# vmon-and-imon-measurements-hw.net
KiCad netlist of a schematic drawn in Altium Designer
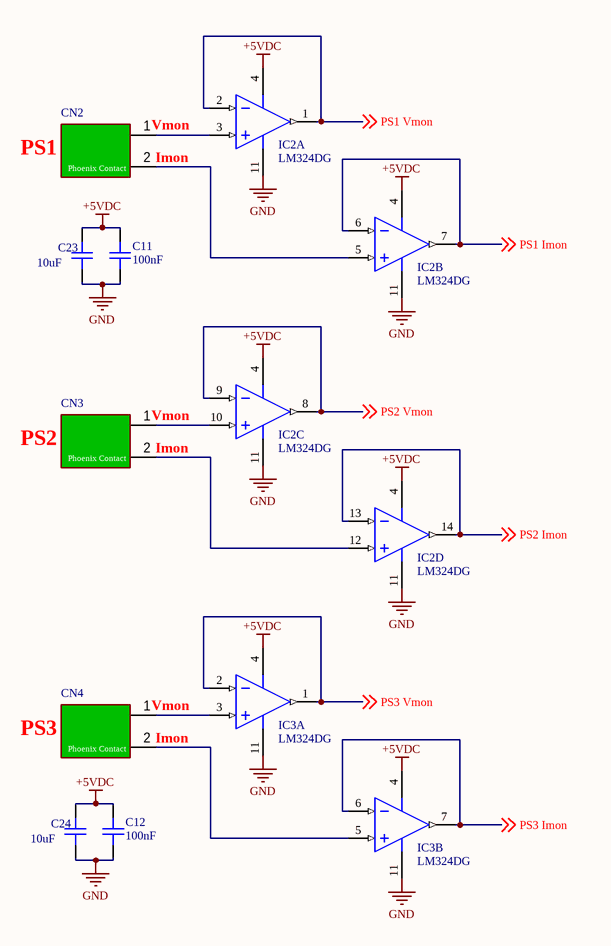
[diagram p0: vmon-and-imon-measurements-hw.SchDoc]

(export (version "E")
  (design (tool "Eeschema 10.0.6"))
  (components
    (comp (ref "C11")
      (value "100nF")
      (footprint "C0805")
      (description "Capacitor 0.1UF 50V X7R 0805")
      (fields (field (name "TOLERANCE") "10%") (field (name "VOLTAGE") "50V"))
      (libsource (lib "acopians-monitoring-hw-library-schematic") (part "CAPACITOR 100nF/50V"))
    )
    (comp (ref "C12")
      (value "100nF")
      (footprint "C0805")
      (description "Capacitor 0.1UF 50V X7R 0805")
      (fields (field (name "TOLERANCE") "10%") (field (name "VOLTAGE") "50V"))
      (libsource (lib "acopians-monitoring-hw-library-schematic") (part "CAPACITOR 100nF/50V"))
    )
    (comp (ref "C23")
      (value "10uF")
      (footprint "C0805")
      (description "Capacitor 10UF 35V X5R 0805")
      (fields
        (field (name "MANUFACTURER") "TDK")
        (field (name "MANUFACTURER PART NUMBER") "C2012X5R1V106K085AC")
      )
      (libsource (lib "acopians-monitoring-hw-library-schematic") (part "CAPACITOR 10uF/35V"))
    )
    (comp (ref "C24")
      (value "10uF")
      (footprint "C0805")
      (description "Capacitor 10UF 35V X5R 0805")
      (fields
        (field (name "MANUFACTURER") "TDK")
        (field (name "MANUFACTURER PART NUMBER") "C2012X5R1V106K085AC")
      )
      (libsource (lib "acopians-monitoring-hw-library-schematic") (part "CAPACITOR 10uF/35V"))
    )
    (comp (ref "CN2")
      (value "1755736")
      (footprint "Conector Phoenix 2 vias 1755736")
      (description "Conector Phoenix 2 vias 1755736")
      (fields (field (name "MANUFACTURER") "Phoenix Contact"))
      (libsource (lib "acopians-monitoring-hw-library-schematic") (part "CONECTOR PHOENIX 2 VIAS 1755736"))
    )
    (comp (ref "CN3")
      (value "1755736")
      (footprint "Conector Phoenix 2 vias 1755736")
      (description "Conector Phoenix 2 vias 1755736")
      (fields (field (name "MANUFACTURER") "Phoenix Contact"))
      (libsource (lib "acopians-monitoring-hw-library-schematic") (part "CONECTOR PHOENIX 2 VIAS 1755736"))
    )
    (comp (ref "CN4")
      (value "1755736")
      (footprint "Conector Phoenix 2 vias 1755736")
      (description "Conector Phoenix 2 vias 1755736")
      (fields (field (name "MANUFACTURER") "Phoenix Contact"))
      (libsource (lib "acopians-monitoring-hw-library-schematic") (part "CONECTOR PHOENIX 2 VIAS 1755736"))
    )
    (comp (ref "IC2")
      (value "LM324DG")
      (footprint "SOIC-14")
      (description "Operational Amplifiers - Op Amps 3-32V Quad 5mV")
      (libsource (lib "acopians-monitoring-hw-library-schematic") (part "LM324DG"))
    )
    (comp (ref "IC3")
      (value "LM324DG")
      (footprint "SOIC-14")
      (description "Operational Amplifiers - Op Amps 3-32V Quad 5mV")
      (libsource (lib "acopians-monitoring-hw-library-schematic") (part "LM324DG"))
    )
  )
  (nets
    (net (code "1") (name "+5VDC") (class "Default")
      (node (ref "C11") (pin "2") (pinfunction "2_2") (pintype "passive"))
      (node (ref "C12") (pin "2") (pinfunction "2_2") (pintype "passive"))
      (node (ref "C23") (pin "1") (pinfunction "1_1") (pintype "passive"))
      (node (ref "C24") (pin "1") (pinfunction "1_1") (pintype "passive"))
      (node (ref "IC2") (pin "4") (pinfunction "V+_4") (pintype "power_in"))
      (node (ref "IC3") (pin "4") (pinfunction "V+_4") (pintype "power_in"))
    )
    (net (code "2") (name "GND") (class "Default")
      (node (ref "C11") (pin "1") (pinfunction "1_1") (pintype "passive"))
      (node (ref "C12") (pin "1") (pinfunction "1_1") (pintype "passive"))
      (node (ref "C23") (pin "2") (pinfunction "2_2") (pintype "passive"))
      (node (ref "C24") (pin "2") (pinfunction "2_2") (pintype "passive"))
      (node (ref "IC2") (pin "11") (pinfunction "V-_11") (pintype "power_in"))
      (node (ref "IC3") (pin "11") (pinfunction "V-_11") (pintype "power_in"))
    )
    (net (code "3") (name "Net-(IC2A-IN_A+)") (class "Default")
      (node (ref "CN2") (pin "1") (pinfunction "1_1") (pintype "passive"))
      (node (ref "IC2") (pin "3") (pinfunction "IN_A+_3") (pintype "input"))
    )
    (net (code "4") (name "Net-(IC2B-IN_B+)") (class "Default")
      (node (ref "CN2") (pin "2") (pinfunction "2_2") (pintype "passive"))
      (node (ref "IC2") (pin "5") (pinfunction "IN_B+_5") (pintype "input"))
    )
    (net (code "5") (name "Net-(IC2C-IN_C+)") (class "Default")
      (node (ref "CN3") (pin "1") (pinfunction "1_1") (pintype "passive"))
      (node (ref "IC2") (pin "10") (pinfunction "IN_C+_10") (pintype "input"))
    )
    (net (code "6") (name "Net-(IC2D-IN_D+)") (class "Default")
      (node (ref "CN3") (pin "2") (pinfunction "2_2") (pintype "passive"))
      (node (ref "IC2") (pin "12") (pinfunction "IN_D+_12") (pintype "input"))
    )
    (net (code "7") (name "Net-(IC3A-IN_A+)") (class "Default")
      (node (ref "CN4") (pin "1") (pinfunction "1_1") (pintype "passive"))
      (node (ref "IC3") (pin "3") (pinfunction "IN_A+_3") (pintype "input"))
    )
    (net (code "8") (name "Net-(IC3B-IN_B+)") (class "Default")
      (node (ref "CN4") (pin "2") (pinfunction "2_2") (pintype "passive"))
      (node (ref "IC3") (pin "5") (pinfunction "IN_B+_5") (pintype "input"))
    )
    (net (code "9") (name "PS1 Imon") (class "Default")
      (node (ref "IC2") (pin "6") (pinfunction "IN_B-_6") (pintype "input"))
      (node (ref "IC2") (pin "7") (pinfunction "OUT_B_7") (pintype "output"))
    )
    (net (code "10") (name "PS1 Vmon") (class "Default")
      (node (ref "IC2") (pin "1") (pinfunction "OUT_A_1") (pintype "output"))
      (node (ref "IC2") (pin "2") (pinfunction "IN_A-_2") (pintype "input"))
    )
    (net (code "11") (name "PS2 Imon") (class "Default")
      (node (ref "IC2") (pin "13") (pinfunction "IN_D-_13") (pintype "input"))
      (node (ref "IC2") (pin "14") (pinfunction "OUT_D_14") (pintype "output"))
    )
    (net (code "12") (name "PS2 Vmon") (class "Default")
      (node (ref "IC2") (pin "8") (pinfunction "OUT_C_8") (pintype "output"))
      (node (ref "IC2") (pin "9") (pinfunction "IN_C-_9") (pintype "input"))
    )
    (net (code "13") (name "PS3 Imon") (class "Default")
      (node (ref "IC3") (pin "6") (pinfunction "IN_B-_6") (pintype "input"))
      (node (ref "IC3") (pin "7") (pinfunction "OUT_B_7") (pintype "output"))
    )
    (net (code "14") (name "PS3 Vmon") (class "Default")
      (node (ref "IC3") (pin "1") (pinfunction "OUT_A_1") (pintype "output"))
      (node (ref "IC3") (pin "2") (pinfunction "IN_A-_2") (pintype "input"))
    )
  )
)
